# RPi_Argon_WateringSystem.net
KiCad netlist of a schematic drawn in EasyEDA
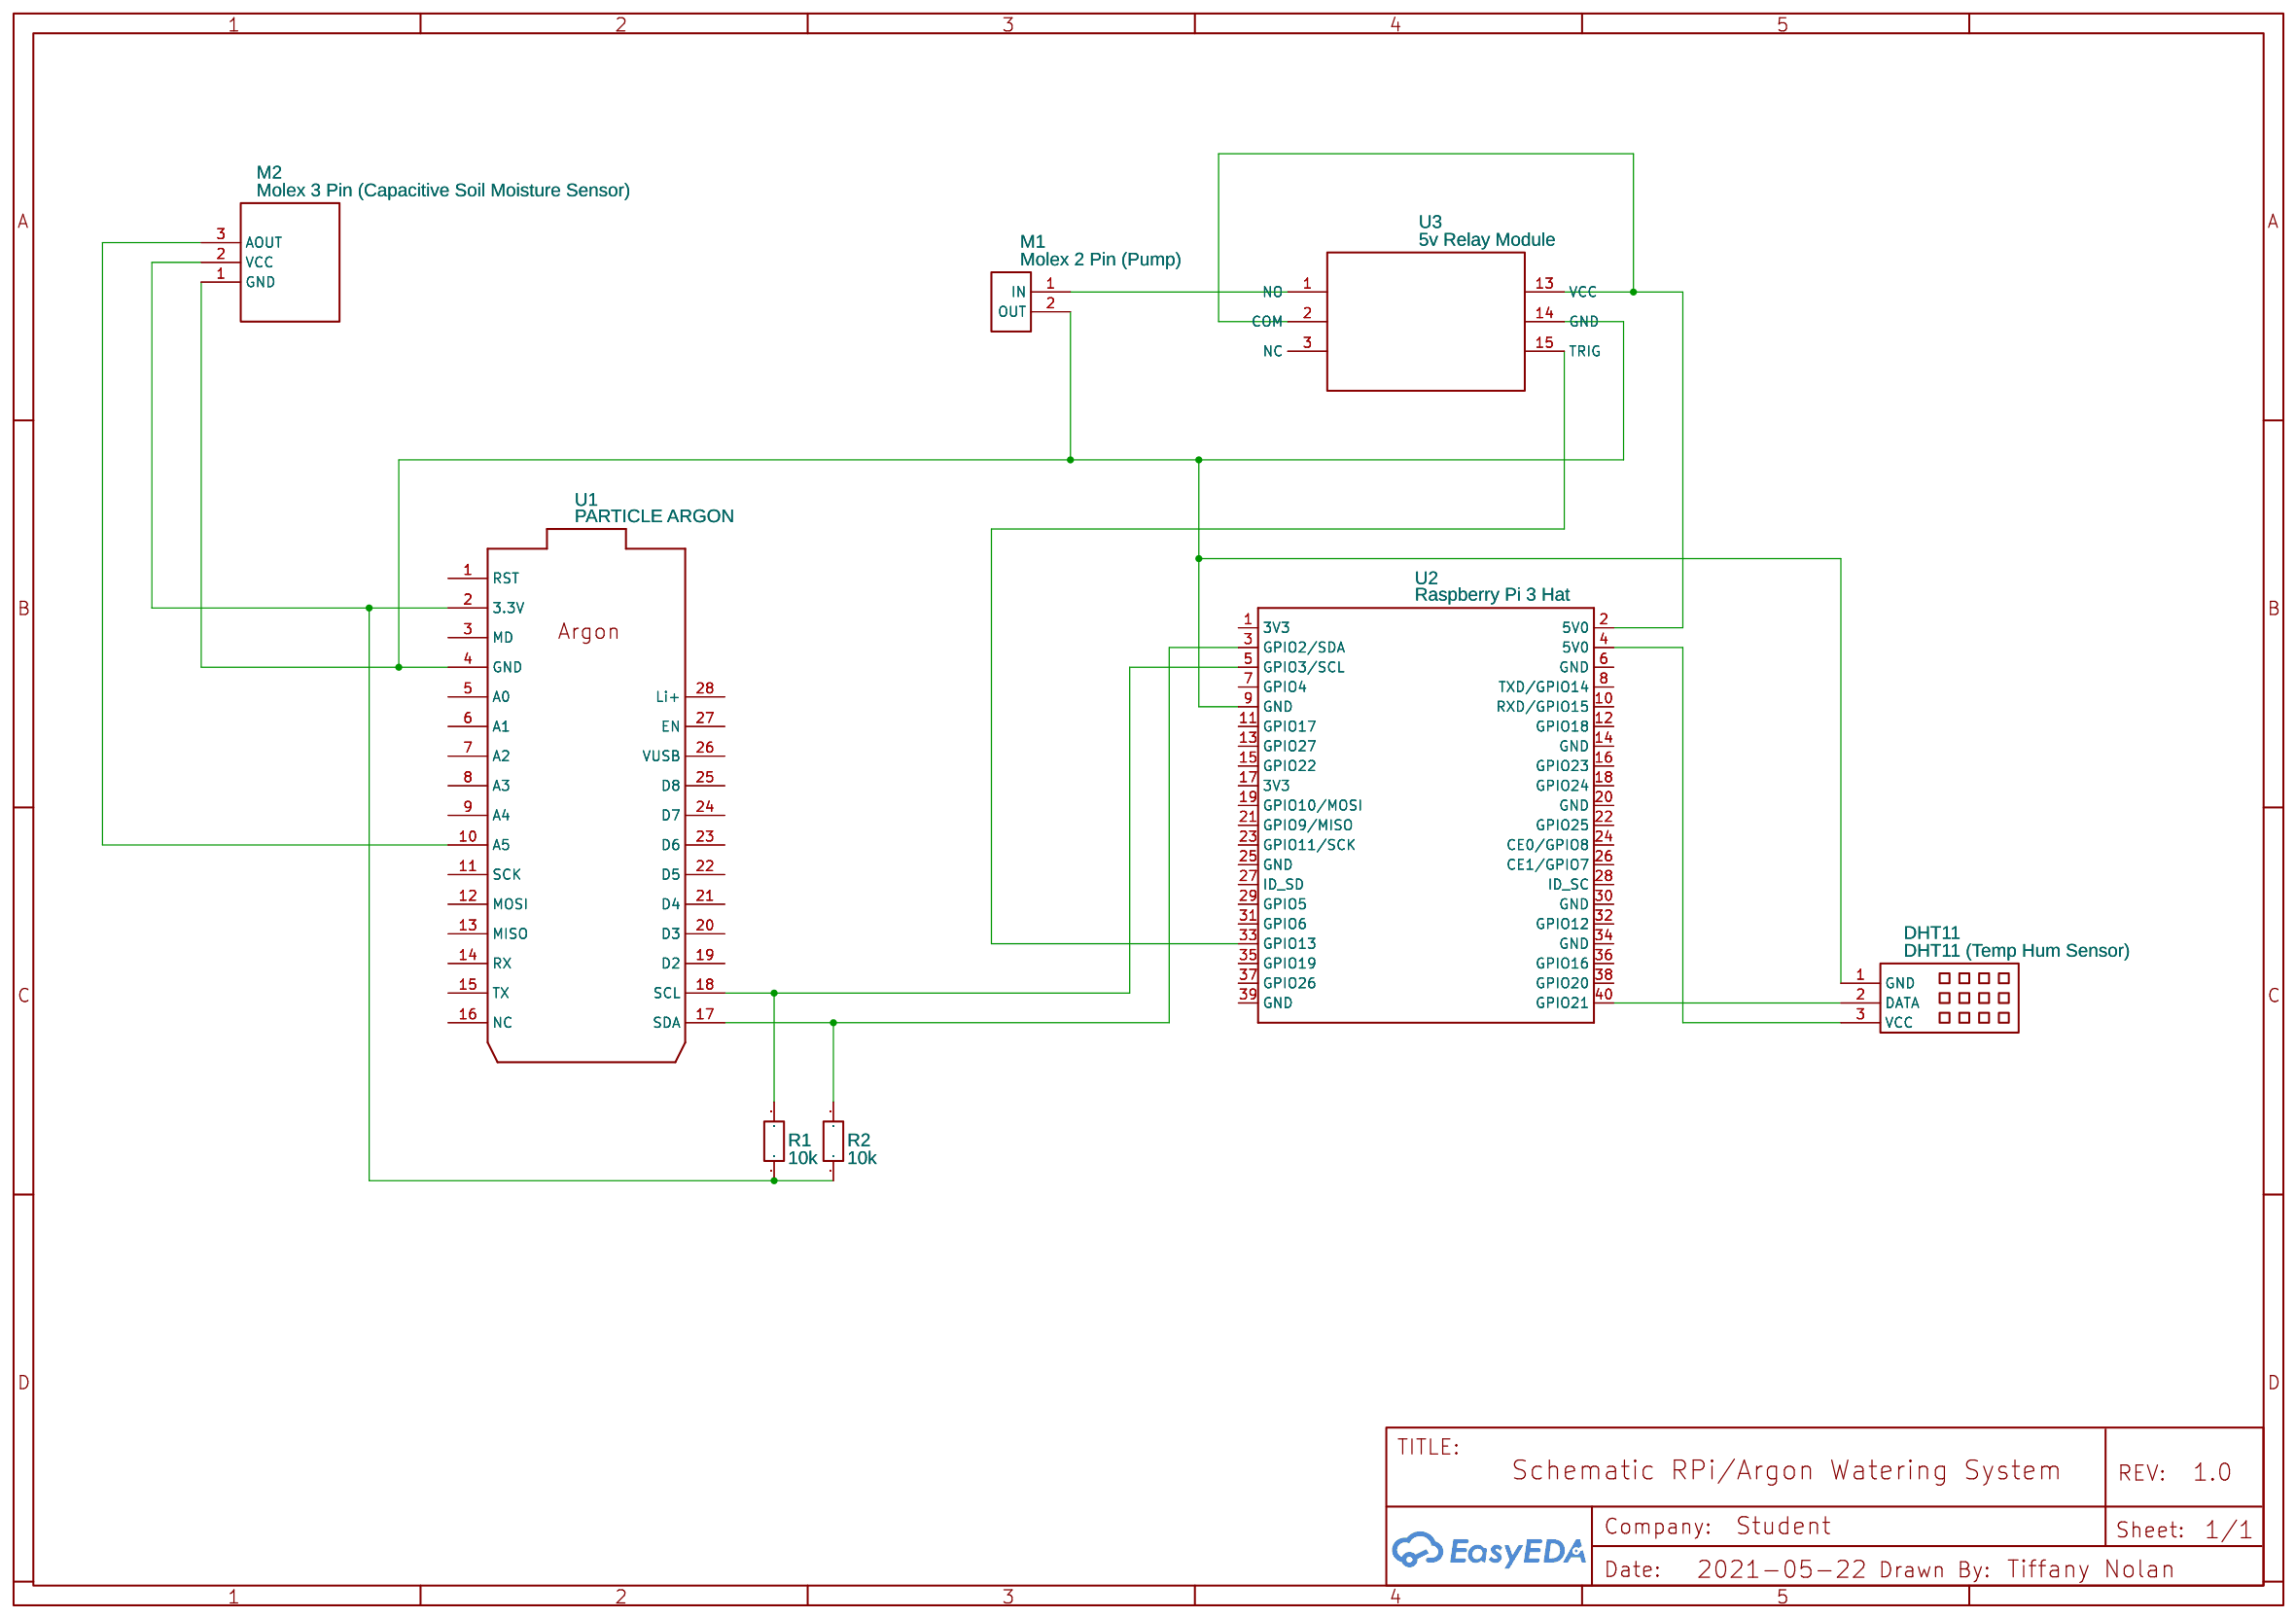
[diagram p0: schematic sheet]

(export (version "E")
  (design (tool "Eeschema 10.0.6"))
  (components
    (comp (ref "DHT11")
      (value "DHT11 (Temp Hum Sensor)")
      (fields (field (name "BOM_Manufacturer Part") "DS18B20+") (field (name "BOM_Supplier Part") "C9753"))
      (libsource (lib "") (part "DHT11"))
    )
    (comp (ref "M1") (value "Molex 2 Pin (Pump)") (libsource (lib "") (part "Molex 2 Pin")))
    (comp (ref "M2")
      (value "Molex 3 Pin (Capacitive Soil Moisture Sensor)")
      (fields (field (name "BOM_Manufacturer Part") "Capacitive Soil Moisture Sensor v1.2"))
      (libsource (lib "") (part "Capacitive Soil Moisture Sensor v1.2"))
    )
    (comp (ref "R1") (value "10k") (libsource (lib "") (part "R_0603_EU")))
    (comp (ref "R2") (value "10k") (libsource (lib "") (part "R_0603_EU")))
    (comp (ref "U1")
      (value "PARTICLE ARGON")
      (fields (field (name "BOM_Manufacturer Part") "Particle Argon"))
      (libsource (lib "") (part "PARTICLE ARGON"))
    )
    (comp (ref "U2")
      (value "Raspberry Pi 3 Hat")
      (fields (field (name "BOM_Manufacturer Part") "RaspberryPi 3"))
      (libsource (lib "") (part "Raspberry Pi 3 Hat"))
    )
    (comp (ref "U3") (value "5v Relay Module") (libsource (lib "") (part "12v Relay Module")))
  )
  (nets
    (net (code "1") (name "Net-(DHT11-DATA)") (class "Default")
      (node (ref "DHT11") (pin "2") (pinfunction "DATA_2") (pintype "unspecified"))
      (node (ref "U2") (pin "40") (pinfunction "GPIO21_40") (pintype "unspecified"))
    )
    (net (code "2") (name "Net-(DHT11-GND)") (class "Default")
      (node (ref "DHT11") (pin "1") (pinfunction "GND_1") (pintype "unspecified"))
      (node (ref "M1") (pin "2") (pinfunction "OUT_2") (pintype "unspecified"))
      (node (ref "M2") (pin "1") (pinfunction "GND_1") (pintype "unspecified"))
      (node (ref "U1") (pin "4") (pinfunction "GND_4") (pintype "unspecified"))
      (node (ref "U2") (pin "9") (pinfunction "GND_9") (pintype "unspecified"))
    )
    (net (code "3") (name "Net-(DHT11-VCC)") (class "Default")
      (node (ref "DHT11") (pin "3") (pinfunction "VCC_3") (pintype "unspecified"))
      (node (ref "U2") (pin "4") (pinfunction "5V0_4") (pintype "unspecified"))
    )
    (net (code "4") (name "Net-(M2-AOUT)") (class "Default")
      (node (ref "M2") (pin "3") (pinfunction "AOUT_3") (pintype "unspecified"))
      (node (ref "U1") (pin "10") (pinfunction "A5_10") (pintype "unspecified"))
    )
    (net (code "5") (name "Net-(M2-VCC)") (class "Default")
      (node (ref "M2") (pin "2") (pinfunction "VCC_2") (pintype "unspecified"))
      (node (ref "R1") (pin "1") (pinfunction "1_1") (pintype "unspecified"))
      (node (ref "R2") (pin "1") (pinfunction "1_1") (pintype "unspecified"))
      (node (ref "U1") (pin "2") (pinfunction "3.3V_2") (pintype "unspecified"))
    )
    (net (code "6") (name "Net-(U1-SCL)") (class "Default")
      (node (ref "R1") (pin "2") (pinfunction "2_2") (pintype "unspecified"))
      (node (ref "U1") (pin "18") (pinfunction "SCL_18") (pintype "unspecified"))
      (node (ref "U2") (pin "5") (pinfunction "GPIO3/SCL_5") (pintype "unspecified"))
    )
    (net (code "7") (name "Net-(U1-SDA)") (class "Default")
      (node (ref "R2") (pin "2") (pinfunction "2_2") (pintype "unspecified"))
      (node (ref "U1") (pin "17") (pinfunction "SDA_17") (pintype "unspecified"))
      (node (ref "U2") (pin "3") (pinfunction "GPIO2/SDA_3") (pintype "unspecified"))
    )
    (net (code "8") (name "unconnected-(M1-IN-Pad1)") (class "Default")
      (node (ref "M1") (pin "1") (pinfunction "IN_1") (pintype "unspecified"))
    )
    (net (code "9") (name "unconnected-(U1-A0-Pad5)") (class "Default")
      (node (ref "U1") (pin "5") (pinfunction "A0_5") (pintype "unspecified"))
    )
    (net (code "10") (name "unconnected-(U1-A1-Pad6)") (class "Default")
      (node (ref "U1") (pin "6") (pinfunction "A1_6") (pintype "unspecified"))
    )
    (net (code "11") (name "unconnected-(U1-A2-Pad7)") (class "Default")
      (node (ref "U1") (pin "7") (pinfunction "A2_7") (pintype "unspecified"))
    )
    (net (code "12") (name "unconnected-(U1-A3-Pad8)") (class "Default")
      (node (ref "U1") (pin "8") (pinfunction "A3_8") (pintype "unspecified"))
    )
    (net (code "13") (name "unconnected-(U1-A4-Pad9)") (class "Default")
      (node (ref "U1") (pin "9") (pinfunction "A4_9") (pintype "unspecified"))
    )
    (net (code "14") (name "unconnected-(U1-D2-Pad19)") (class "Default")
      (node (ref "U1") (pin "19") (pinfunction "D2_19") (pintype "unspecified"))
    )
    (net (code "15") (name "unconnected-(U1-D3-Pad20)") (class "Default")
      (node (ref "U1") (pin "20") (pinfunction "D3_20") (pintype "unspecified"))
    )
    (net (code "16") (name "unconnected-(U1-D4-Pad21)") (class "Default")
      (node (ref "U1") (pin "21") (pinfunction "D4_21") (pintype "unspecified"))
    )
    (net (code "17") (name "unconnected-(U1-D5-Pad22)") (class "Default")
      (node (ref "U1") (pin "22") (pinfunction "D5_22") (pintype "unspecified"))
    )
    (net (code "18") (name "unconnected-(U1-D6-Pad23)") (class "Default")
      (node (ref "U1") (pin "23") (pinfunction "D6_23") (pintype "unspecified"))
    )
    (net (code "19") (name "unconnected-(U1-D7-Pad24)") (class "Default")
      (node (ref "U1") (pin "24") (pinfunction "D7_24") (pintype "unspecified"))
    )
    (net (code "20") (name "unconnected-(U1-D8-Pad25)") (class "Default")
      (node (ref "U1") (pin "25") (pinfunction "D8_25") (pintype "unspecified"))
    )
    (net (code "21") (name "unconnected-(U1-EN-Pad27)") (class "Default")
      (node (ref "U1") (pin "27") (pinfunction "EN_27") (pintype "unspecified"))
    )
    (net (code "22") (name "unconnected-(U1-Li+-Pad28)") (class "Default")
      (node (ref "U1") (pin "28") (pinfunction "Li+_28") (pintype "unspecified"))
    )
    (net (code "23") (name "unconnected-(U1-MD-Pad3)") (class "Default")
      (node (ref "U1") (pin "3") (pinfunction "MD_3") (pintype "unspecified"))
    )
    (net (code "24") (name "unconnected-(U1-MISO-Pad13)") (class "Default")
      (node (ref "U1") (pin "13") (pinfunction "MISO_13") (pintype "unspecified"))
    )
    (net (code "25") (name "unconnected-(U1-MOSI-Pad12)") (class "Default")
      (node (ref "U1") (pin "12") (pinfunction "MOSI_12") (pintype "unspecified"))
    )
    (net (code "26") (name "unconnected-(U1-NC-Pad16)") (class "Default")
      (node (ref "U1") (pin "16") (pinfunction "NC_16") (pintype "unspecified"))
    )
    (net (code "27") (name "unconnected-(U1-RST-Pad1)") (class "Default")
      (node (ref "U1") (pin "1") (pinfunction "RST_1") (pintype "unspecified"))
    )
    (net (code "28") (name "unconnected-(U1-RX-Pad14)") (class "Default")
      (node (ref "U1") (pin "14") (pinfunction "RX_14") (pintype "unspecified"))
    )
    (net (code "29") (name "unconnected-(U1-SCK-Pad11)") (class "Default")
      (node (ref "U1") (pin "11") (pinfunction "SCK_11") (pintype "unspecified"))
    )
    (net (code "30") (name "unconnected-(U1-TX-Pad15)") (class "Default")
      (node (ref "U1") (pin "15") (pinfunction "TX_15") (pintype "unspecified"))
    )
    (net (code "31") (name "unconnected-(U1-VUSB-Pad26)") (class "Default")
      (node (ref "U1") (pin "26") (pinfunction "VUSB_26") (pintype "unspecified"))
    )
    (net (code "32") (name "unconnected-(U2-3V3-Pad1)") (class "Default")
      (node (ref "U2") (pin "1") (pinfunction "3V3_1") (pintype "unspecified"))
    )
    (net (code "33") (name "unconnected-(U2-3V3-Pad17)") (class "Default")
      (node (ref "U2") (pin "17") (pinfunction "3V3_17") (pintype "unspecified"))
    )
    (net (code "34") (name "unconnected-(U2-5V0-Pad2)") (class "Default")
      (node (ref "U2") (pin "2") (pinfunction "5V0_2") (pintype "unspecified"))
    )
    (net (code "35") (name "unconnected-(U2-CE0{slash}GPIO8-Pad24)") (class "Default")
      (node (ref "U2") (pin "24") (pinfunction "CE0/GPIO8_24") (pintype "unspecified"))
    )
    (net (code "36") (name "unconnected-(U2-CE1{slash}GPIO7-Pad26)") (class "Default")
      (node (ref "U2") (pin "26") (pinfunction "CE1/GPIO7_26") (pintype "unspecified"))
    )
    (net (code "37") (name "unconnected-(U2-GND-Pad6)") (class "Default")
      (node (ref "U2") (pin "6") (pinfunction "GND_6") (pintype "unspecified"))
    )
    (net (code "38") (name "unconnected-(U2-GND-Pad14)") (class "Default")
      (node (ref "U2") (pin "14") (pinfunction "GND_14") (pintype "unspecified"))
    )
    (net (code "39") (name "unconnected-(U2-GND-Pad20)") (class "Default")
      (node (ref "U2") (pin "20") (pinfunction "GND_20") (pintype "unspecified"))
    )
    (net (code "40") (name "unconnected-(U2-GND-Pad25)") (class "Default")
      (node (ref "U2") (pin "25") (pinfunction "GND_25") (pintype "unspecified"))
    )
    (net (code "41") (name "unconnected-(U2-GND-Pad30)") (class "Default")
      (node (ref "U2") (pin "30") (pinfunction "GND_30") (pintype "unspecified"))
    )
    (net (code "42") (name "unconnected-(U2-GND-Pad34)") (class "Default")
      (node (ref "U2") (pin "34") (pinfunction "GND_34") (pintype "unspecified"))
    )
    (net (code "43") (name "unconnected-(U2-GND-Pad39)") (class "Default")
      (node (ref "U2") (pin "39") (pinfunction "GND_39") (pintype "unspecified"))
    )
    (net (code "44") (name "unconnected-(U2-GPIO4-Pad7)") (class "Default")
      (node (ref "U2") (pin "7") (pinfunction "GPIO4_7") (pintype "unspecified"))
    )
    (net (code "45") (name "unconnected-(U2-GPIO5-Pad29)") (class "Default")
      (node (ref "U2") (pin "29") (pinfunction "GPIO5_29") (pintype "unspecified"))
    )
    (net (code "46") (name "unconnected-(U2-GPIO6-Pad31)") (class "Default")
      (node (ref "U2") (pin "31") (pinfunction "GPIO6_31") (pintype "unspecified"))
    )
    (net (code "47") (name "unconnected-(U2-GPIO9{slash}MISO-Pad21)") (class "Default")
      (node (ref "U2") (pin "21") (pinfunction "GPIO9/MISO_21") (pintype "unspecified"))
    )
    (net (code "48") (name "unconnected-(U2-GPIO10{slash}MOSI-Pad19)") (class "Default")
      (node (ref "U2") (pin "19") (pinfunction "GPIO10/MOSI_19") (pintype "unspecified"))
    )
    (net (code "49") (name "unconnected-(U2-GPIO11{slash}SCK-Pad23)") (class "Default")
      (node (ref "U2") (pin "23") (pinfunction "GPIO11/SCK_23") (pintype "unspecified"))
    )
    (net (code "50") (name "unconnected-(U2-GPIO12-Pad32)") (class "Default")
      (node (ref "U2") (pin "32") (pinfunction "GPIO12_32") (pintype "unspecified"))
    )
    (net (code "51") (name "unconnected-(U2-GPIO13-Pad33)") (class "Default")
      (node (ref "U2") (pin "33") (pinfunction "GPIO13_33") (pintype "unspecified"))
    )
    (net (code "52") (name "unconnected-(U2-GPIO16-Pad36)") (class "Default")
      (node (ref "U2") (pin "36") (pinfunction "GPIO16_36") (pintype "unspecified"))
    )
    (net (code "53") (name "unconnected-(U2-GPIO17-Pad11)") (class "Default")
      (node (ref "U2") (pin "11") (pinfunction "GPIO17_11") (pintype "unspecified"))
    )
    (net (code "54") (name "unconnected-(U2-GPIO18-Pad12)") (class "Default")
      (node (ref "U2") (pin "12") (pinfunction "GPIO18_12") (pintype "unspecified"))
    )
    (net (code "55") (name "unconnected-(U2-GPIO19-Pad35)") (class "Default")
      (node (ref "U2") (pin "35") (pinfunction "GPIO19_35") (pintype "unspecified"))
    )
    (net (code "56") (name "unconnected-(U2-GPIO20-Pad38)") (class "Default")
      (node (ref "U2") (pin "38") (pinfunction "GPIO20_38") (pintype "unspecified"))
    )
    (net (code "57") (name "unconnected-(U2-GPIO22-Pad15)") (class "Default")
      (node (ref "U2") (pin "15") (pinfunction "GPIO22_15") (pintype "unspecified"))
    )
    (net (code "58") (name "unconnected-(U2-GPIO23-Pad16)") (class "Default")
      (node (ref "U2") (pin "16") (pinfunction "GPIO23_16") (pintype "unspecified"))
    )
    (net (code "59") (name "unconnected-(U2-GPIO24-Pad18)") (class "Default")
      (node (ref "U2") (pin "18") (pinfunction "GPIO24_18") (pintype "unspecified"))
    )
    (net (code "60") (name "unconnected-(U2-GPIO25-Pad22)") (class "Default")
      (node (ref "U2") (pin "22") (pinfunction "GPIO25_22") (pintype "unspecified"))
    )
    (net (code "61") (name "unconnected-(U2-GPIO26-Pad37)") (class "Default")
      (node (ref "U2") (pin "37") (pinfunction "GPIO26_37") (pintype "unspecified"))
    )
    (net (code "62") (name "unconnected-(U2-GPIO27-Pad13)") (class "Default")
      (node (ref "U2") (pin "13") (pinfunction "GPIO27_13") (pintype "unspecified"))
    )
    (net (code "63") (name "unconnected-(U2-ID_SC-Pad28)") (class "Default")
      (node (ref "U2") (pin "28") (pinfunction "ID_SC_28") (pintype "unspecified"))
    )
    (net (code "64") (name "unconnected-(U2-ID_SD-Pad27)") (class "Default")
      (node (ref "U2") (pin "27") (pinfunction "ID_SD_27") (pintype "unspecified"))
    )
    (net (code "65") (name "unconnected-(U2-RXD{slash}GPIO15-Pad10)") (class "Default")
      (node (ref "U2") (pin "10") (pinfunction "RXD/GPIO15_10") (pintype "unspecified"))
    )
    (net (code "66") (name "unconnected-(U2-TXD{slash}GPIO14-Pad8)") (class "Default")
      (node (ref "U2") (pin "8") (pinfunction "TXD/GPIO14_8") (pintype "unspecified"))
    )
    (net (code "67") (name "unconnected-(U3-COM-Pad2)") (class "Default")
      (node (ref "U3") (pin "2") (pinfunction "COM_2") (pintype "unspecified"))
    )
    (net (code "68") (name "unconnected-(U3-GND-Pad14)") (class "Default")
      (node (ref "U3") (pin "14") (pinfunction "GND_14") (pintype "unspecified"))
    )
    (net (code "69") (name "unconnected-(U3-NC-Pad3)") (class "Default")
      (node (ref "U3") (pin "3") (pinfunction "NC_3") (pintype "unspecified"))
    )
    (net (code "70") (name "unconnected-(U3-NO-Pad1)") (class "Default")
      (node (ref "U3") (pin "1") (pinfunction "NO_1") (pintype "unspecified"))
    )
    (net (code "71") (name "unconnected-(U3-TRIG-Pad15)") (class "Default")
      (node (ref "U3") (pin "15") (pinfunction "TRIG_15") (pintype "unspecified"))
    )
    (net (code "72") (name "unconnected-(U3-VCC-Pad13)") (class "Default")
      (node (ref "U3") (pin "13") (pinfunction "VCC_13") (pintype "unspecified"))
    )
  )
)
